# MIU60_REVB.net
KiCad netlist of a schematic drawn in EAGLE
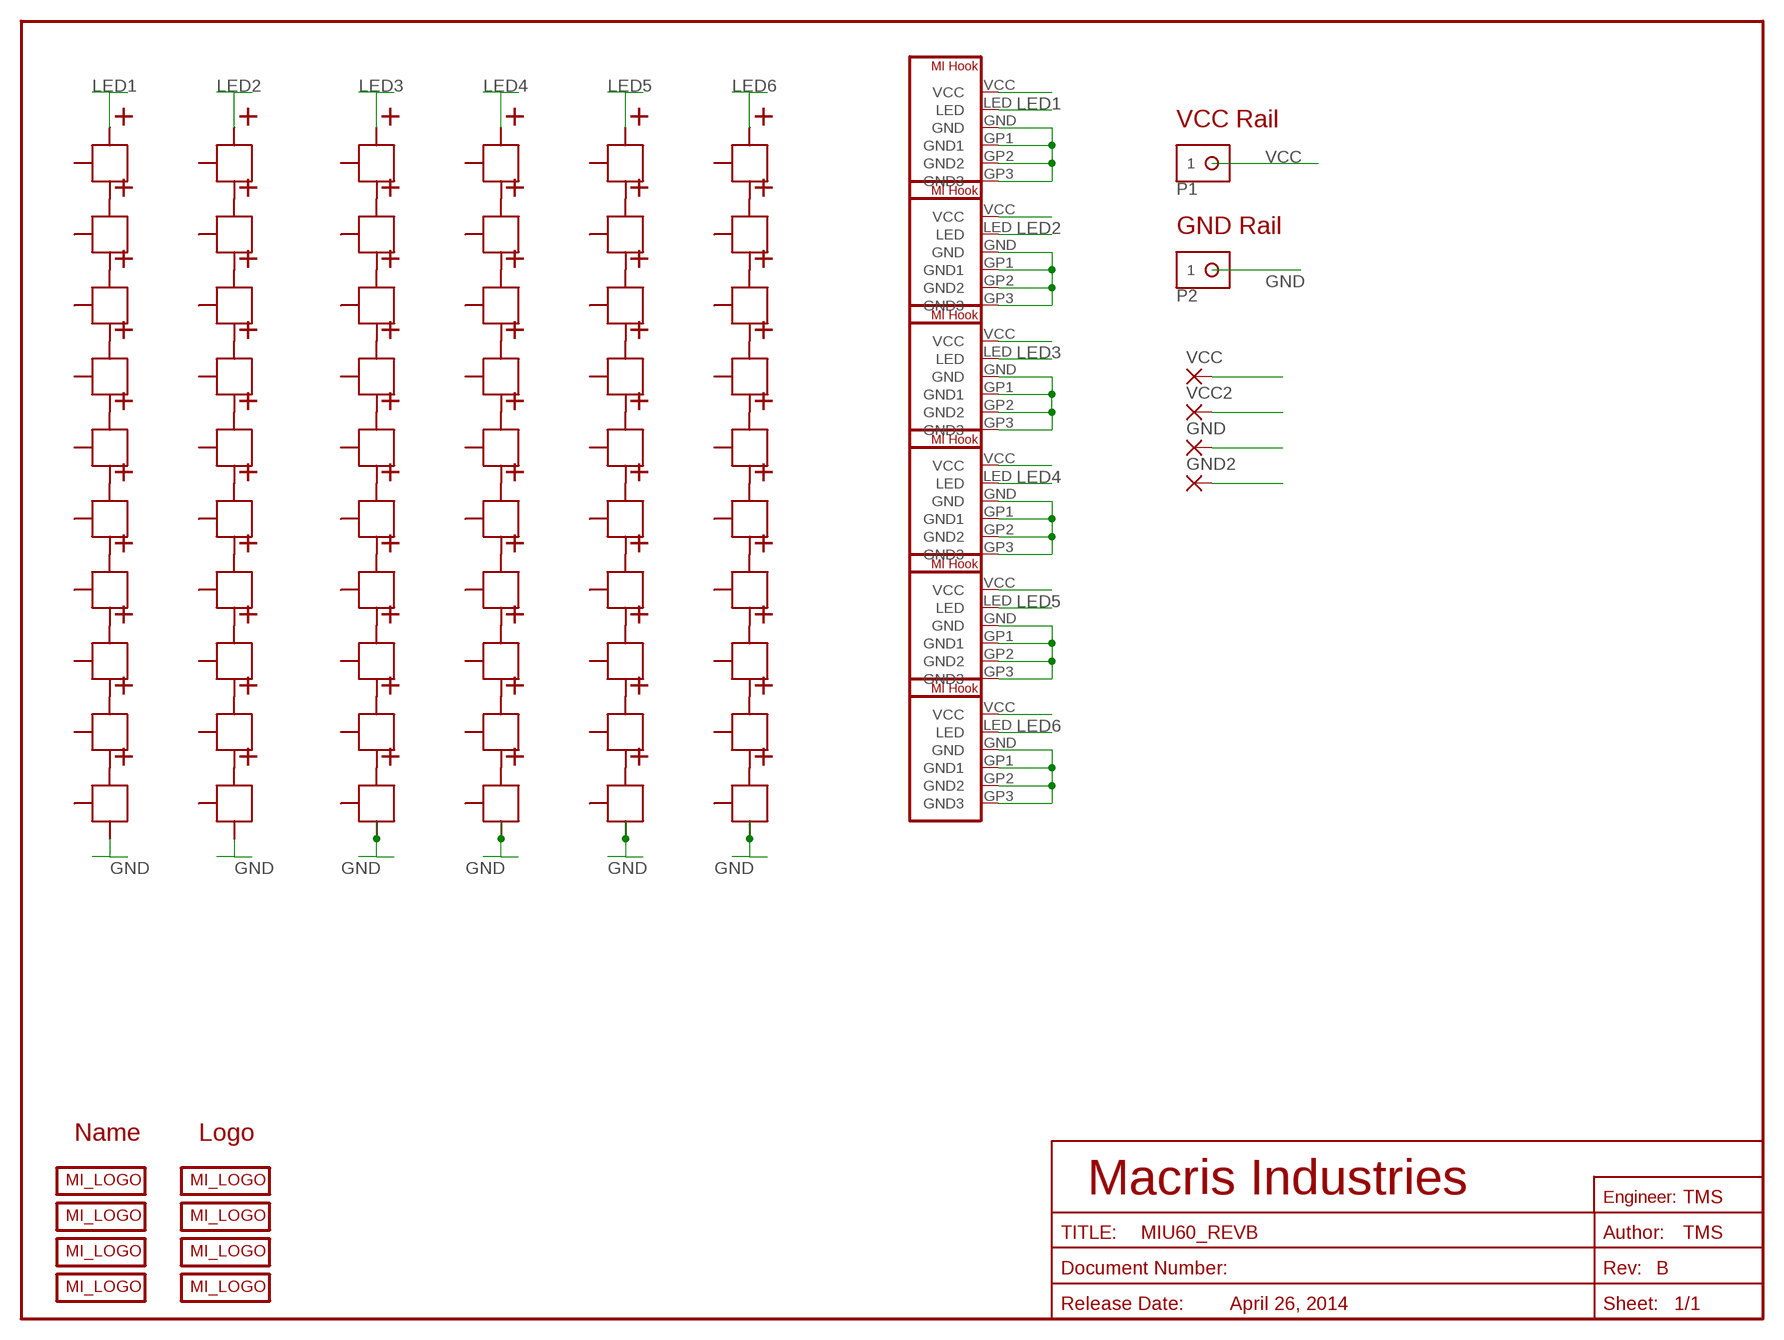
[diagram p0: schematic, sheet 1]

(export (version "E")
  (design (tool "Eeschema 10.0.6"))
  (components
    (comp (ref "GND")
      (value "SMD5")
      (footprint "eagle-import:SMD2,54-5,08")
      (libsource (lib "eagle-import") (part "SMD5"))
    )
    (comp (ref "GND2")
      (value "SMD5")
      (footprint "eagle-import:SMD2,54-5,08")
      (libsource (lib "eagle-import") (part "SMD5"))
    )
    (comp (ref "P1")
      (value "PAD-10G")
      (footprint "eagle-import:PAD_10G")
      (libsource (lib "eagle-import") (part "PAD-10G"))
    )
    (comp (ref "P2")
      (value "PAD-10G")
      (footprint "eagle-import:PAD_10G")
      (libsource (lib "eagle-import") (part "PAD-10G"))
    )
    (comp (ref "U$1")
      (value "MI_LOGO-50MIL")
      (footprint "eagle-import:MI_LOGO_NAME_2")
      (libsource (lib "eagle-import") (part "MI_LOGO-NAME_TWO"))
    )
    (comp (ref "U$2")
      (value "MI_LOGO-2014_USA")
      (footprint "eagle-import:MACRIS_USA_LOGO")
      (libsource (lib "eagle-import") (part "MI_LOGO-2014_USA"))
    )
    (comp (ref "U$3")
      (value "MI_LOGO-50MIL")
      (footprint "eagle-import:MI_LOGO_NAME_2")
      (libsource (lib "eagle-import") (part "MI_LOGO-NAME_TWO"))
    )
    (comp (ref "U$4")
      (value "MI_LOGO-2014_USA")
      (footprint "eagle-import:MACRIS_USA_LOGO")
      (libsource (lib "eagle-import") (part "MI_LOGO-2014_USA"))
    )
    (comp (ref "U$5")
      (value "MI_LOGO-50MIL")
      (footprint "eagle-import:MI_LOGO_NAME_2")
      (libsource (lib "eagle-import") (part "MI_LOGO-NAME_TWO"))
    )
    (comp (ref "U$6")
      (value "MI_LOGO-50MIL")
      (footprint "eagle-import:MI_LOGO_NAME_2")
      (libsource (lib "eagle-import") (part "MI_LOGO-NAME_TWO"))
    )
    (comp (ref "U$7")
      (value "MI_LOGO-2014_USA")
      (footprint "eagle-import:MACRIS_USA_LOGO")
      (libsource (lib "eagle-import") (part "MI_LOGO-2014_USA"))
    )
    (comp (ref "U$8")
      (value "MI_LOGO-2014_USA")
      (footprint "eagle-import:MACRIS_USA_LOGO")
      (libsource (lib "eagle-import") (part "MI_LOGO-2014_USA"))
    )
    (comp (ref "U$9")
      (value "MI_DRIVER_HOOKUP")
      (footprint "eagle-import:MI_DRIVE_HOOKUP")
      (libsource (lib "eagle-import") (part "MI_DRIVER_HOOKUP"))
    )
    (comp (ref "U$10")
      (value "MI_DRIVER_HOOKUP")
      (footprint "eagle-import:MI_DRIVE_HOOKUP")
      (libsource (lib "eagle-import") (part "MI_DRIVER_HOOKUP"))
    )
    (comp (ref "U$11")
      (value "MI_DRIVER_HOOKUP")
      (footprint "eagle-import:MI_DRIVE_HOOKUP")
      (libsource (lib "eagle-import") (part "MI_DRIVER_HOOKUP"))
    )
    (comp (ref "U$12")
      (value "MI_DRIVER_HOOKUP")
      (footprint "eagle-import:MI_DRIVE_HOOKUP")
      (libsource (lib "eagle-import") (part "MI_DRIVER_HOOKUP"))
    )
    (comp (ref "U$13")
      (value "MI_DRIVER_HOOKUP")
      (footprint "eagle-import:MI_DRIVE_HOOKUP")
      (libsource (lib "eagle-import") (part "MI_DRIVER_HOOKUP"))
    )
    (comp (ref "U$14")
      (value "MI_DRIVER_HOOKUP")
      (footprint "eagle-import:MI_DRIVE_HOOKUP")
      (libsource (lib "eagle-import") (part "MI_DRIVER_HOOKUP"))
    )
    (comp (ref "U$16")
      (value "CREE_XP")
      (footprint "eagle-import:XP")
      (libsource (lib "eagle-import") (part "CREE_XP"))
    )
    (comp (ref "U$17")
      (value "CREE_XP")
      (footprint "eagle-import:XP")
      (libsource (lib "eagle-import") (part "CREE_XP"))
    )
    (comp (ref "U$18")
      (value "CREE_XP")
      (footprint "eagle-import:XP")
      (libsource (lib "eagle-import") (part "CREE_XP"))
    )
    (comp (ref "U$19")
      (value "CREE_XP")
      (footprint "eagle-import:XP")
      (libsource (lib "eagle-import") (part "CREE_XP"))
    )
    (comp (ref "U$20")
      (value "CREE_XP")
      (footprint "eagle-import:XP")
      (libsource (lib "eagle-import") (part "CREE_XP"))
    )
    (comp (ref "U$21")
      (value "CREE_XP")
      (footprint "eagle-import:XP")
      (libsource (lib "eagle-import") (part "CREE_XP"))
    )
    (comp (ref "U$22")
      (value "CREE_XP")
      (footprint "eagle-import:XP")
      (libsource (lib "eagle-import") (part "CREE_XP"))
    )
    (comp (ref "U$23")
      (value "CREE_XP")
      (footprint "eagle-import:XP")
      (libsource (lib "eagle-import") (part "CREE_XP"))
    )
    (comp (ref "U$24")
      (value "CREE_XP")
      (footprint "eagle-import:XP")
      (libsource (lib "eagle-import") (part "CREE_XP"))
    )
    (comp (ref "U$25")
      (value "CREE_XP")
      (footprint "eagle-import:XP")
      (libsource (lib "eagle-import") (part "CREE_XP"))
    )
    (comp (ref "U$26")
      (value "CREE_XP")
      (footprint "eagle-import:XP")
      (libsource (lib "eagle-import") (part "CREE_XP"))
    )
    (comp (ref "U$27")
      (value "CREE_XP")
      (footprint "eagle-import:XP")
      (libsource (lib "eagle-import") (part "CREE_XP"))
    )
    (comp (ref "U$28")
      (value "CREE_XP")
      (footprint "eagle-import:XP")
      (libsource (lib "eagle-import") (part "CREE_XP"))
    )
    (comp (ref "U$29")
      (value "CREE_XP")
      (footprint "eagle-import:XP")
      (libsource (lib "eagle-import") (part "CREE_XP"))
    )
    (comp (ref "U$30")
      (value "CREE_XP")
      (footprint "eagle-import:XP")
      (libsource (lib "eagle-import") (part "CREE_XP"))
    )
    (comp (ref "U$31")
      (value "CREE_XP")
      (footprint "eagle-import:XP")
      (libsource (lib "eagle-import") (part "CREE_XP"))
    )
    (comp (ref "U$32")
      (value "CREE_XP")
      (footprint "eagle-import:XP")
      (libsource (lib "eagle-import") (part "CREE_XP"))
    )
    (comp (ref "U$33")
      (value "CREE_XP")
      (footprint "eagle-import:XP")
      (libsource (lib "eagle-import") (part "CREE_XP"))
    )
    (comp (ref "U$34")
      (value "CREE_XP")
      (footprint "eagle-import:XP")
      (libsource (lib "eagle-import") (part "CREE_XP"))
    )
    (comp (ref "U$35")
      (value "CREE_XP")
      (footprint "eagle-import:XP")
      (libsource (lib "eagle-import") (part "CREE_XP"))
    )
    (comp (ref "U$36")
      (value "CREE_XP")
      (footprint "eagle-import:XP")
      (libsource (lib "eagle-import") (part "CREE_XP"))
    )
    (comp (ref "U$37")
      (value "CREE_XP")
      (footprint "eagle-import:XP")
      (libsource (lib "eagle-import") (part "CREE_XP"))
    )
    (comp (ref "U$38")
      (value "CREE_XP")
      (footprint "eagle-import:XP")
      (libsource (lib "eagle-import") (part "CREE_XP"))
    )
    (comp (ref "U$39")
      (value "CREE_XP")
      (footprint "eagle-import:XP")
      (libsource (lib "eagle-import") (part "CREE_XP"))
    )
    (comp (ref "U$40")
      (value "CREE_XP")
      (footprint "eagle-import:XP")
      (libsource (lib "eagle-import") (part "CREE_XP"))
    )
    (comp (ref "U$41")
      (value "CREE_XP")
      (footprint "eagle-import:XP")
      (libsource (lib "eagle-import") (part "CREE_XP"))
    )
    (comp (ref "U$42")
      (value "CREE_XP")
      (footprint "eagle-import:XP")
      (libsource (lib "eagle-import") (part "CREE_XP"))
    )
    (comp (ref "U$43")
      (value "CREE_XP")
      (footprint "eagle-import:XP")
      (libsource (lib "eagle-import") (part "CREE_XP"))
    )
    (comp (ref "U$44")
      (value "CREE_XP")
      (footprint "eagle-import:XP")
      (libsource (lib "eagle-import") (part "CREE_XP"))
    )
    (comp (ref "U$45")
      (value "CREE_XP")
      (footprint "eagle-import:XP")
      (libsource (lib "eagle-import") (part "CREE_XP"))
    )
    (comp (ref "U$46")
      (value "CREE_XP")
      (footprint "eagle-import:XP")
      (libsource (lib "eagle-import") (part "CREE_XP"))
    )
    (comp (ref "U$47")
      (value "CREE_XP")
      (footprint "eagle-import:XP")
      (libsource (lib "eagle-import") (part "CREE_XP"))
    )
    (comp (ref "U$48")
      (value "CREE_XP")
      (footprint "eagle-import:XP")
      (libsource (lib "eagle-import") (part "CREE_XP"))
    )
    (comp (ref "U$49")
      (value "CREE_XP")
      (footprint "eagle-import:XP")
      (libsource (lib "eagle-import") (part "CREE_XP"))
    )
    (comp (ref "U$50")
      (value "CREE_XP")
      (footprint "eagle-import:XP")
      (libsource (lib "eagle-import") (part "CREE_XP"))
    )
    (comp (ref "U$51")
      (value "CREE_XP")
      (footprint "eagle-import:XP")
      (libsource (lib "eagle-import") (part "CREE_XP"))
    )
    (comp (ref "U$52")
      (value "CREE_XP")
      (footprint "eagle-import:XP")
      (libsource (lib "eagle-import") (part "CREE_XP"))
    )
    (comp (ref "U$53")
      (value "CREE_XP")
      (footprint "eagle-import:XP")
      (libsource (lib "eagle-import") (part "CREE_XP"))
    )
    (comp (ref "U$54")
      (value "CREE_XP")
      (footprint "eagle-import:XP")
      (libsource (lib "eagle-import") (part "CREE_XP"))
    )
    (comp (ref "U$55")
      (value "CREE_XP")
      (footprint "eagle-import:XP")
      (libsource (lib "eagle-import") (part "CREE_XP"))
    )
    (comp (ref "U$56")
      (value "CREE_XP")
      (footprint "eagle-import:XP")
      (libsource (lib "eagle-import") (part "CREE_XP"))
    )
    (comp (ref "U$57")
      (value "CREE_XP")
      (footprint "eagle-import:XP")
      (libsource (lib "eagle-import") (part "CREE_XP"))
    )
    (comp (ref "U$58")
      (value "CREE_XP")
      (footprint "eagle-import:XP")
      (libsource (lib "eagle-import") (part "CREE_XP"))
    )
    (comp (ref "U$59")
      (value "CREE_XP")
      (footprint "eagle-import:XP")
      (libsource (lib "eagle-import") (part "CREE_XP"))
    )
    (comp (ref "U$60")
      (value "CREE_XP")
      (footprint "eagle-import:XP")
      (libsource (lib "eagle-import") (part "CREE_XP"))
    )
    (comp (ref "U$61")
      (value "CREE_XP")
      (footprint "eagle-import:XP")
      (libsource (lib "eagle-import") (part "CREE_XP"))
    )
    (comp (ref "U$62")
      (value "CREE_XP")
      (footprint "eagle-import:XP")
      (libsource (lib "eagle-import") (part "CREE_XP"))
    )
    (comp (ref "U$63")
      (value "CREE_XP")
      (footprint "eagle-import:XP")
      (libsource (lib "eagle-import") (part "CREE_XP"))
    )
    (comp (ref "U$64")
      (value "CREE_XP")
      (footprint "eagle-import:XP")
      (libsource (lib "eagle-import") (part "CREE_XP"))
    )
    (comp (ref "U$65")
      (value "CREE_XP")
      (footprint "eagle-import:XP")
      (libsource (lib "eagle-import") (part "CREE_XP"))
    )
    (comp (ref "U$66")
      (value "CREE_XP")
      (footprint "eagle-import:XP")
      (libsource (lib "eagle-import") (part "CREE_XP"))
    )
    (comp (ref "U$67")
      (value "CREE_XP")
      (footprint "eagle-import:XP")
      (libsource (lib "eagle-import") (part "CREE_XP"))
    )
    (comp (ref "U$68")
      (value "CREE_XP")
      (footprint "eagle-import:XP")
      (libsource (lib "eagle-import") (part "CREE_XP"))
    )
    (comp (ref "U$69")
      (value "CREE_XP")
      (footprint "eagle-import:XP")
      (libsource (lib "eagle-import") (part "CREE_XP"))
    )
    (comp (ref "U$70")
      (value "CREE_XP")
      (footprint "eagle-import:XP")
      (libsource (lib "eagle-import") (part "CREE_XP"))
    )
    (comp (ref "U$71")
      (value "CREE_XP")
      (footprint "eagle-import:XP")
      (libsource (lib "eagle-import") (part "CREE_XP"))
    )
    (comp (ref "U$72")
      (value "CREE_XP")
      (footprint "eagle-import:XP")
      (libsource (lib "eagle-import") (part "CREE_XP"))
    )
    (comp (ref "U$73")
      (value "CREE_XP")
      (footprint "eagle-import:XP")
      (libsource (lib "eagle-import") (part "CREE_XP"))
    )
    (comp (ref "U$74")
      (value "CREE_XP")
      (footprint "eagle-import:XP")
      (libsource (lib "eagle-import") (part "CREE_XP"))
    )
    (comp (ref "U$75")
      (value "CREE_XP")
      (footprint "eagle-import:XP")
      (libsource (lib "eagle-import") (part "CREE_XP"))
    )
    (comp (ref "VCC")
      (value "SMD5")
      (footprint "eagle-import:SMD2,54-5,08")
      (libsource (lib "eagle-import") (part "SMD5"))
    )
    (comp (ref "VCC2")
      (value "SMD5")
      (footprint "eagle-import:SMD2,54-5,08")
      (libsource (lib "eagle-import") (part "SMD5"))
    )
  )
  (nets
    (net (code "1") (name "/GND") (class "Default")
      (node (ref "GND") (pin "1") (pinfunction "P_1") (pintype "passive"))
      (node (ref "GND2") (pin "1") (pinfunction "P_1") (pintype "passive"))
      (node (ref "P2") (pin "1") (pinfunction "1_1") (pintype "passive"))
      (node (ref "U$10") (pin "GND") (pinfunction "GND_GND") (pintype "bidirectional"))
      (node (ref "U$10") (pin "GP1") (pinfunction "GND1_GP1") (pintype "bidirectional"))
      (node (ref "U$10") (pin "GP2") (pinfunction "GND2_GP2") (pintype "bidirectional"))
      (node (ref "U$10") (pin "GP3") (pinfunction "GND3_GP3") (pintype "bidirectional"))
      (node (ref "U$11") (pin "GND") (pinfunction "GND_GND") (pintype "bidirectional"))
      (node (ref "U$11") (pin "GP1") (pinfunction "GND1_GP1") (pintype "bidirectional"))
      (node (ref "U$11") (pin "GP2") (pinfunction "GND2_GP2") (pintype "bidirectional"))
      (node (ref "U$11") (pin "GP3") (pinfunction "GND3_GP3") (pintype "bidirectional"))
      (node (ref "U$12") (pin "GND") (pinfunction "GND_GND") (pintype "bidirectional"))
      (node (ref "U$12") (pin "GP1") (pinfunction "GND1_GP1") (pintype "bidirectional"))
      (node (ref "U$12") (pin "GP2") (pinfunction "GND2_GP2") (pintype "bidirectional"))
      (node (ref "U$12") (pin "GP3") (pinfunction "GND3_GP3") (pintype "bidirectional"))
      (node (ref "U$13") (pin "GND") (pinfunction "GND_GND") (pintype "bidirectional"))
      (node (ref "U$13") (pin "GP1") (pinfunction "GND1_GP1") (pintype "bidirectional"))
      (node (ref "U$13") (pin "GP2") (pinfunction "GND2_GP2") (pintype "bidirectional"))
      (node (ref "U$13") (pin "GP3") (pinfunction "GND3_GP3") (pintype "bidirectional"))
      (node (ref "U$14") (pin "GND") (pinfunction "GND_GND") (pintype "bidirectional"))
      (node (ref "U$14") (pin "GP1") (pinfunction "GND1_GP1") (pintype "bidirectional"))
      (node (ref "U$14") (pin "GP2") (pinfunction "GND2_GP2") (pintype "bidirectional"))
      (node (ref "U$14") (pin "GP3") (pinfunction "GND3_GP3") (pintype "bidirectional"))
      (node (ref "U$25") (pin "NEGATIVE") (pinfunction "NEGATIVE_NEGATIVE") (pintype "bidirectional"))
      (node (ref "U$25") (pin "NEGATIVE1") (pinfunction "NEGATIVE_NEGATIVE1") (pintype "bidirectional"))
      (node (ref "U$35") (pin "NEGATIVE") (pinfunction "NEGATIVE_NEGATIVE") (pintype "bidirectional"))
      (node (ref "U$35") (pin "NEGATIVE1") (pinfunction "NEGATIVE_NEGATIVE1") (pintype "bidirectional"))
      (node (ref "U$45") (pin "NEGATIVE") (pinfunction "NEGATIVE_NEGATIVE") (pintype "bidirectional"))
      (node (ref "U$45") (pin "NEGATIVE1") (pinfunction "NEGATIVE_NEGATIVE1") (pintype "bidirectional"))
      (node (ref "U$55") (pin "NEGATIVE") (pinfunction "NEGATIVE_NEGATIVE") (pintype "bidirectional"))
      (node (ref "U$55") (pin "NEGATIVE1") (pinfunction "NEGATIVE_NEGATIVE1") (pintype "bidirectional"))
      (node (ref "U$65") (pin "NEGATIVE") (pinfunction "NEGATIVE_NEGATIVE") (pintype "bidirectional"))
      (node (ref "U$65") (pin "NEGATIVE1") (pinfunction "NEGATIVE_NEGATIVE1") (pintype "bidirectional"))
      (node (ref "U$75") (pin "NEGATIVE") (pinfunction "NEGATIVE_NEGATIVE") (pintype "bidirectional"))
      (node (ref "U$75") (pin "NEGATIVE1") (pinfunction "NEGATIVE_NEGATIVE1") (pintype "bidirectional"))
      (node (ref "U$9") (pin "GND") (pinfunction "GND_GND") (pintype "bidirectional"))
      (node (ref "U$9") (pin "GP1") (pinfunction "GND1_GP1") (pintype "bidirectional"))
      (node (ref "U$9") (pin "GP2") (pinfunction "GND2_GP2") (pintype "bidirectional"))
      (node (ref "U$9") (pin "GP3") (pinfunction "GND3_GP3") (pintype "bidirectional"))
    )
    (net (code "2") (name "/LED1") (class "Default")
      (node (ref "U$16") (pin "POSITIVE") (pinfunction "POSITIVE_POSITIVE") (pintype "bidirectional"))
      (node (ref "U$16") (pin "POSITIVE1") (pinfunction "POSITIVE_POSITIVE1") (pintype "bidirectional"))
      (node (ref "U$9") (pin "LED") (pinfunction "LED_LED") (pintype "bidirectional"))
    )
    (net (code "3") (name "/LED2") (class "Default")
      (node (ref "U$10") (pin "LED") (pinfunction "LED_LED") (pintype "bidirectional"))
      (node (ref "U$26") (pin "POSITIVE") (pinfunction "POSITIVE_POSITIVE") (pintype "bidirectional"))
      (node (ref "U$26") (pin "POSITIVE1") (pinfunction "POSITIVE_POSITIVE1") (pintype "bidirectional"))
    )
    (net (code "4") (name "/LED3") (class "Default")
      (node (ref "U$11") (pin "LED") (pinfunction "LED_LED") (pintype "bidirectional"))
      (node (ref "U$36") (pin "POSITIVE") (pinfunction "POSITIVE_POSITIVE") (pintype "bidirectional"))
      (node (ref "U$36") (pin "POSITIVE1") (pinfunction "POSITIVE_POSITIVE1") (pintype "bidirectional"))
    )
    (net (code "5") (name "/LED4") (class "Default")
      (node (ref "U$12") (pin "LED") (pinfunction "LED_LED") (pintype "bidirectional"))
      (node (ref "U$46") (pin "POSITIVE") (pinfunction "POSITIVE_POSITIVE") (pintype "bidirectional"))
      (node (ref "U$46") (pin "POSITIVE1") (pinfunction "POSITIVE_POSITIVE1") (pintype "bidirectional"))
    )
    (net (code "6") (name "/LED5") (class "Default")
      (node (ref "U$13") (pin "LED") (pinfunction "LED_LED") (pintype "bidirectional"))
      (node (ref "U$56") (pin "POSITIVE") (pinfunction "POSITIVE_POSITIVE") (pintype "bidirectional"))
      (node (ref "U$56") (pin "POSITIVE1") (pinfunction "POSITIVE_POSITIVE1") (pintype "bidirectional"))
    )
    (net (code "7") (name "/LED6") (class "Default")
      (node (ref "U$14") (pin "LED") (pinfunction "LED_LED") (pintype "bidirectional"))
      (node (ref "U$66") (pin "POSITIVE") (pinfunction "POSITIVE_POSITIVE") (pintype "bidirectional"))
      (node (ref "U$66") (pin "POSITIVE1") (pinfunction "POSITIVE_POSITIVE1") (pintype "bidirectional"))
    )
    (net (code "8") (name "/VCC") (class "Default")
      (node (ref "P1") (pin "1") (pinfunction "1_1") (pintype "passive"))
      (node (ref "U$10") (pin "VCC") (pinfunction "VCC_VCC") (pintype "bidirectional"))
      (node (ref "U$11") (pin "VCC") (pinfunction "VCC_VCC") (pintype "bidirectional"))
      (node (ref "U$12") (pin "VCC") (pinfunction "VCC_VCC") (pintype "bidirectional"))
      (node (ref "U$13") (pin "VCC") (pinfunction "VCC_VCC") (pintype "bidirectional"))
      (node (ref "U$14") (pin "VCC") (pinfunction "VCC_VCC") (pintype "bidirectional"))
      (node (ref "U$9") (pin "VCC") (pinfunction "VCC_VCC") (pintype "bidirectional"))
      (node (ref "VCC") (pin "1") (pinfunction "P_1") (pintype "passive"))
      (node (ref "VCC2") (pin "1") (pinfunction "P_1") (pintype "passive"))
    )
    (net (code "9") (name "Net-(U$16-NEGATIVE-PadNEGATIVE1)") (class "Default")
      (node (ref "U$16") (pin "NEGATIVE") (pinfunction "NEGATIVE_NEGATIVE") (pintype "bidirectional"))
      (node (ref "U$16") (pin "NEGATIVE1") (pinfunction "NEGATIVE_NEGATIVE1") (pintype "bidirectional"))
      (node (ref "U$17") (pin "POSITIVE") (pinfunction "POSITIVE_POSITIVE") (pintype "bidirectional"))
      (node (ref "U$17") (pin "POSITIVE1") (pinfunction "POSITIVE_POSITIVE1") (pintype "bidirectional"))
    )
    (net (code "10") (name "Net-(U$17-NEGATIVE-PadNEGATIVE1)") (class "Default")
      (node (ref "U$17") (pin "NEGATIVE") (pinfunction "NEGATIVE_NEGATIVE") (pintype "bidirectional"))
      (node (ref "U$17") (pin "NEGATIVE1") (pinfunction "NEGATIVE_NEGATIVE1") (pintype "bidirectional"))
      (node (ref "U$18") (pin "POSITIVE") (pinfunction "POSITIVE_POSITIVE") (pintype "bidirectional"))
      (node (ref "U$18") (pin "POSITIVE1") (pinfunction "POSITIVE_POSITIVE1") (pintype "bidirectional"))
    )
    (net (code "11") (name "Net-(U$18-NEGATIVE-PadNEGATIVE1)") (class "Default")
      (node (ref "U$18") (pin "NEGATIVE") (pinfunction "NEGATIVE_NEGATIVE") (pintype "bidirectional"))
      (node (ref "U$18") (pin "NEGATIVE1") (pinfunction "NEGATIVE_NEGATIVE1") (pintype "bidirectional"))
      (node (ref "U$19") (pin "POSITIVE") (pinfunction "POSITIVE_POSITIVE") (pintype "bidirectional"))
      (node (ref "U$19") (pin "POSITIVE1") (pinfunction "POSITIVE_POSITIVE1") (pintype "bidirectional"))
    )
    (net (code "12") (name "Net-(U$19-NEGATIVE-PadNEGATIVE1)") (class "Default")
      (node (ref "U$19") (pin "NEGATIVE") (pinfunction "NEGATIVE_NEGATIVE") (pintype "bidirectional"))
      (node (ref "U$19") (pin "NEGATIVE1") (pinfunction "NEGATIVE_NEGATIVE1") (pintype "bidirectional"))
      (node (ref "U$20") (pin "POSITIVE") (pinfunction "POSITIVE_POSITIVE") (pintype "bidirectional"))
      (node (ref "U$20") (pin "POSITIVE1") (pinfunction "POSITIVE_POSITIVE1") (pintype "bidirectional"))
    )
    (net (code "13") (name "Net-(U$20-NEGATIVE-PadNEGATIVE1)") (class "Default")
      (node (ref "U$20") (pin "NEGATIVE") (pinfunction "NEGATIVE_NEGATIVE") (pintype "bidirectional"))
      (node (ref "U$20") (pin "NEGATIVE1") (pinfunction "NEGATIVE_NEGATIVE1") (pintype "bidirectional"))
      (node (ref "U$21") (pin "POSITIVE") (pinfunction "POSITIVE_POSITIVE") (pintype "bidirectional"))
      (node (ref "U$21") (pin "POSITIVE1") (pinfunction "POSITIVE_POSITIVE1") (pintype "bidirectional"))
    )
    (net (code "14") (name "Net-(U$21-NEGATIVE-PadNEGATIVE1)") (class "Default")
      (node (ref "U$21") (pin "NEGATIVE") (pinfunction "NEGATIVE_NEGATIVE") (pintype "bidirectional"))
      (node (ref "U$21") (pin "NEGATIVE1") (pinfunction "NEGATIVE_NEGATIVE1") (pintype "bidirectional"))
      (node (ref "U$22") (pin "POSITIVE") (pinfunction "POSITIVE_POSITIVE") (pintype "bidirectional"))
      (node (ref "U$22") (pin "POSITIVE1") (pinfunction "POSITIVE_POSITIVE1") (pintype "bidirectional"))
    )
    (net (code "15") (name "Net-(U$22-NEGATIVE-PadNEGATIVE1)") (class "Default")
      (node (ref "U$22") (pin "NEGATIVE") (pinfunction "NEGATIVE_NEGATIVE") (pintype "bidirectional"))
      (node (ref "U$22") (pin "NEGATIVE1") (pinfunction "NEGATIVE_NEGATIVE1") (pintype "bidirectional"))
      (node (ref "U$23") (pin "POSITIVE") (pinfunction "POSITIVE_POSITIVE") (pintype "bidirectional"))
      (node (ref "U$23") (pin "POSITIVE1") (pinfunction "POSITIVE_POSITIVE1") (pintype "bidirectional"))
    )
    (net (code "16") (name "Net-(U$23-NEGATIVE-PadNEGATIVE1)") (class "Default")
      (node (ref "U$23") (pin "NEGATIVE") (pinfunction "NEGATIVE_NEGATIVE") (pintype "bidirectional"))
      (node (ref "U$23") (pin "NEGATIVE1") (pinfunction "NEGATIVE_NEGATIVE1") (pintype "bidirectional"))
      (node (ref "U$24") (pin "POSITIVE") (pinfunction "POSITIVE_POSITIVE") (pintype "bidirectional"))
      (node (ref "U$24") (pin "POSITIVE1") (pinfunction "POSITIVE_POSITIVE1") (pintype "bidirectional"))
    )
    (net (code "17") (name "Net-(U$24-NEGATIVE-PadNEGATIVE1)") (class "Default")
      (node (ref "U$24") (pin "NEGATIVE") (pinfunction "NEGATIVE_NEGATIVE") (pintype "bidirectional"))
      (node (ref "U$24") (pin "NEGATIVE1") (pinfunction "NEGATIVE_NEGATIVE1") (pintype "bidirectional"))
      (node (ref "U$25") (pin "POSITIVE") (pinfunction "POSITIVE_POSITIVE") (pintype "bidirectional"))
      (node (ref "U$25") (pin "POSITIVE1") (pinfunction "POSITIVE_POSITIVE1") (pintype "bidirectional"))
    )
    (net (code "18") (name "Net-(U$26-NEGATIVE-PadNEGATIVE1)") (class "Default")
      (node (ref "U$26") (pin "NEGATIVE") (pinfunction "NEGATIVE_NEGATIVE") (pintype "bidirectional"))
      (node (ref "U$26") (pin "NEGATIVE1") (pinfunction "NEGATIVE_NEGATIVE1") (pintype "bidirectional"))
      (node (ref "U$27") (pin "POSITIVE") (pinfunction "POSITIVE_POSITIVE") (pintype "bidirectional"))
      (node (ref "U$27") (pin "POSITIVE1") (pinfunction "POSITIVE_POSITIVE1") (pintype "bidirectional"))
    )
    (net (code "19") (name "Net-(U$27-NEGATIVE-PadNEGATIVE1)") (class "Default")
      (node (ref "U$27") (pin "NEGATIVE") (pinfunction "NEGATIVE_NEGATIVE") (pintype "bidirectional"))
      (node (ref "U$27") (pin "NEGATIVE1") (pinfunction "NEGATIVE_NEGATIVE1") (pintype "bidirectional"))
      (node (ref "U$28") (pin "POSITIVE") (pinfunction "POSITIVE_POSITIVE") (pintype "bidirectional"))
      (node (ref "U$28") (pin "POSITIVE1") (pinfunction "POSITIVE_POSITIVE1") (pintype "bidirectional"))
    )
    (net (code "20") (name "Net-(U$28-NEGATIVE-PadNEGATIVE1)") (class "Default")
      (node (ref "U$28") (pin "NEGATIVE") (pinfunction "NEGATIVE_NEGATIVE") (pintype "bidirectional"))
      (node (ref "U$28") (pin "NEGATIVE1") (pinfunction "NEGATIVE_NEGATIVE1") (pintype "bidirectional"))
      (node (ref "U$29") (pin "POSITIVE") (pinfunction "POSITIVE_POSITIVE") (pintype "bidirectional"))
      (node (ref "U$29") (pin "POSITIVE1") (pinfunction "POSITIVE_POSITIVE1") (pintype "bidirectional"))
    )
    (net (code "21") (name "Net-(U$29-NEGATIVE-PadNEGATIVE1)") (class "Default")
      (node (ref "U$29") (pin "NEGATIVE") (pinfunction "NEGATIVE_NEGATIVE") (pintype "bidirectional"))
      (node (ref "U$29") (pin "NEGATIVE1") (pinfunction "NEGATIVE_NEGATIVE1") (pintype "bidirectional"))
      (node (ref "U$30") (pin "POSITIVE") (pinfunction "POSITIVE_POSITIVE") (pintype "bidirectional"))
      (node (ref "U$30") (pin "POSITIVE1") (pinfunction "POSITIVE_POSITIVE1") (pintype "bidirectional"))
    )
    (net (code "22") (name "Net-(U$30-NEGATIVE-PadNEGATIVE1)") (class "Default")
      (node (ref "U$30") (pin "NEGATIVE") (pinfunction "NEGATIVE_NEGATIVE") (pintype "bidirectional"))
      (node (ref "U$30") (pin "NEGATIVE1") (pinfunction "NEGATIVE_NEGATIVE1") (pintype "bidirectional"))
      (node (ref "U$31") (pin "POSITIVE") (pinfunction "POSITIVE_POSITIVE") (pintype "bidirectional"))
      (node (ref "U$31") (pin "POSITIVE1") (pinfunction "POSITIVE_POSITIVE1") (pintype "bidirectional"))
    )
    (net (code "23") (name "Net-(U$31-NEGATIVE-PadNEGATIVE1)") (class "Default")
      (node (ref "U$31") (pin "NEGATIVE") (pinfunction "NEGATIVE_NEGATIVE") (pintype "bidirectional"))
      (node (ref "U$31") (pin "NEGATIVE1") (pinfunction "NEGATIVE_NEGATIVE1") (pintype "bidirectional"))
      (node (ref "U$32") (pin "POSITIVE") (pinfunction "POSITIVE_POSITIVE") (pintype "bidirectional"))
      (node (ref "U$32") (pin "POSITIVE1") (pinfunction "POSITIVE_POSITIVE1") (pintype "bidirectional"))
    )
    (net (code "24") (name "Net-(U$32-NEGATIVE-PadNEGATIVE1)") (class "Default")
      (node (ref "U$32") (pin "NEGATIVE") (pinfunction "NEGATIVE_NEGATIVE") (pintype "bidirectional"))
      (node (ref "U$32") (pin "NEGATIVE1") (pinfunction "NEGATIVE_NEGATIVE1") (pintype "bidirectional"))
      (node (ref "U$33") (pin "POSITIVE") (pinfunction "POSITIVE_POSITIVE") (pintype "bidirectional"))
      (node (ref "U$33") (pin "POSITIVE1") (pinfunction "POSITIVE_POSITIVE1") (pintype "bidirectional"))
    )
    (net (code "25") (name "Net-(U$33-NEGATIVE-PadNEGATIVE1)") (class "Default")
      (node (ref "U$33") (pin "NEGATIVE") (pinfunction "NEGATIVE_NEGATIVE") (pintype "bidirectional"))
      (node (ref "U$33") (pin "NEGATIVE1") (pinfunction "NEGATIVE_NEGATIVE1") (pintype "bidirectional"))
      (node (ref "U$34") (pin "POSITIVE") (pinfunction "POSITIVE_POSITIVE") (pintype "bidirectional"))
      (node (ref "U$34") (pin "POSITIVE1") (pinfunction "POSITIVE_POSITIVE1") (pintype "bidirectional"))
    )
    (net (code "26") (name "Net-(U$34-NEGATIVE-PadNEGATIVE1)") (class "Default")
      (node (ref "U$34") (pin "NEGATIVE") (pinfunction "NEGATIVE_NEGATIVE") (pintype "bidirectional"))
      (node (ref "U$34") (pin "NEGATIVE1") (pinfunction "NEGATIVE_NEGATIVE1") (pintype "bidirectional"))
      (node (ref "U$35") (pin "POSITIVE") (pinfunction "POSITIVE_POSITIVE") (pintype "bidirectional"))
      (node (ref "U$35") (pin "POSITIVE1") (pinfunction "POSITIVE_POSITIVE1") (pintype "bidirectional"))
    )
    (net (code "27") (name "Net-(U$36-NEGATIVE-PadNEGATIVE1)") (class "Default")
      (node (ref "U$36") (pin "NEGATIVE") (pinfunction "NEGATIVE_NEGATIVE") (pintype "bidirectional"))
      (node (ref "U$36") (pin "NEGATIVE1") (pinfunction "NEGATIVE_NEGATIVE1") (pintype "bidirectional"))
      (node (ref "U$37") (pin "POSITIVE") (pinfunction "POSITIVE_POSITIVE") (pintype "bidirectional"))
      (node (ref "U$37") (pin "POSITIVE1") (pinfunction "POSITIVE_POSITIVE1") (pintype "bidirectional"))
    )
    (net (code "28") (name "Net-(U$37-NEGATIVE-PadNEGATIVE1)") (class "Default")
      (node (ref "U$37") (pin "NEGATIVE") (pinfunction "NEGATIVE_NEGATIVE") (pintype "bidirectional"))
      (node (ref "U$37") (pin "NEGATIVE1") (pinfunction "NEGATIVE_NEGATIVE1") (pintype "bidirectional"))
      (node (ref "U$38") (pin "POSITIVE") (pinfunction "POSITIVE_POSITIVE") (pintype "bidirectional"))
      (node (ref "U$38") (pin "POSITIVE1") (pinfunction "POSITIVE_POSITIVE1") (pintype "bidirectional"))
    )
    (net (code "29") (name "Net-(U$38-NEGATIVE-PadNEGATIVE1)") (class "Default")
      (node (ref "U$38") (pin "NEGATIVE") (pinfunction "NEGATIVE_NEGATIVE") (pintype "bidirectional"))
      (node (ref "U$38") (pin "NEGATIVE1") (pinfunction "NEGATIVE_NEGATIVE1") (pintype "bidirectional"))
      (node (ref "U$39") (pin "POSITIVE") (pinfunction "POSITIVE_POSITIVE") (pintype "bidirectional"))
      (node (ref "U$39") (pin "POSITIVE1") (pinfunction "POSITIVE_POSITIVE1") (pintype "bidirectional"))
    )
    (net (code "30") (name "Net-(U$39-NEGATIVE-PadNEGATIVE1)") (class "Default")
      (node (ref "U$39") (pin "NEGATIVE") (pinfunction "NEGATIVE_NEGATIVE") (pintype "bidirectional"))
      (node (ref "U$39") (pin "NEGATIVE1") (pinfunction "NEGATIVE_NEGATIVE1") (pintype "bidirectional"))
      (node (ref "U$40") (pin "POSITIVE") (pinfunction "POSITIVE_POSITIVE") (pintype "bidirectional"))
      (node (ref "U$40") (pin "POSITIVE1") (pinfunction "POSITIVE_POSITIVE1") (pintype "bidirectional"))
    )
    (net (code "31") (name "Net-(U$40-NEGATIVE-PadNEGATIVE1)") (class "Default")
      (node (ref "U$40") (pin "NEGATIVE") (pinfunction "NEGATIVE_NEGATIVE") (pintype "bidirectional"))
      (node (ref "U$40") (pin "NEGATIVE1") (pinfunction "NEGATIVE_NEGATIVE1") (pintype "bidirectional"))
      (node (ref "U$41") (pin "POSITIVE") (pinfunction "POSITIVE_POSITIVE") (pintype "bidirectional"))
      (node (ref "U$41") (pin "POSITIVE1") (pinfunction "POSITIVE_POSITIVE1") (pintype "bidirectional"))
    )
    (net (code "32") (name "Net-(U$41-NEGATIVE-PadNEGATIVE1)") (class "Default")
      (node (ref "U$41") (pin "NEGATIVE") (pinfunction "NEGATIVE_NEGATIVE") (pintype "bidirectional"))
      (node (ref "U$41") (pin "NEGATIVE1") (pinfunction "NEGATIVE_NEGATIVE1") (pintype "bidirectional"))
      (node (ref "U$42") (pin "POSITIVE") (pinfunction "POSITIVE_POSITIVE") (pintype "bidirectional"))
      (node (ref "U$42") (pin "POSITIVE1") (pinfunction "POSITIVE_POSITIVE1") (pintype "bidirectional"))
    )
    (net (code "33") (name "Net-(U$42-NEGATIVE-PadNEGATIVE1)") (class "Default")
      (node (ref "U$42") (pin "NEGATIVE") (pinfunction "NEGATIVE_NEGATIVE") (pintype "bidirectional"))
      (node (ref "U$42") (pin "NEGATIVE1") (pinfunction "NEGATIVE_NEGATIVE1") (pintype "bidirectional"))
      (node (ref "U$43") (pin "POSITIVE") (pinfunction "POSITIVE_POSITIVE") (pintype "bidirectional"))
      (node (ref "U$43") (pin "POSITIVE1") (pinfunction "POSITIVE_POSITIVE1") (pintype "bidirectional"))
    )
    (net (code "34") (name "Net-(U$43-NEGATIVE-PadNEGATIVE1)") (class "Default")
      (node (ref "U$43") (pin "NEGATIVE") (pinfunction "NEGATIVE_NEGATIVE") (pintype "bidirectional"))
      (node (ref "U$43") (pin "NEGATIVE1") (pinfunction "NEGATIVE_NEGATIVE1") (pintype "bidirectional"))
      (node (ref "U$44") (pin "POSITIVE") (pinfunction "POSITIVE_POSITIVE") (pintype "bidirectional"))
      (node (ref "U$44") (pin "POSITIVE1") (pinfunction "POSITIVE_POSITIVE1") (pintype "bidirectional"))
    )
    (net (code "35") (name "Net-(U$44-NEGATIVE-PadNEGATIVE1)") (class "Default")
      (node (ref "U$44") (pin "NEGATIVE") (pinfunction "NEGATIVE_NEGATIVE") (pintype "bidirectional"))
      (node (ref "U$44") (pin "NEGATIVE1") (pinfunction "NEGATIVE_NEGATIVE1") (pintype "bidirectional"))
      (node (ref "U$45") (pin "POSITIVE") (pinfunction "POSITIVE_POSITIVE") (pintype "bidirectional"))
      (node (ref "U$45") (pin "POSITIVE1") (pinfunction "POSITIVE_POSITIVE1") (pintype "bidirectional"))
    )
    (net (code "36") (name "Net-(U$46-NEGATIVE-PadNEGATIVE1)") (class "Default")
      (node (ref "U$46") (pin "NEGATIVE") (pinfunction "NEGATIVE_NEGATIVE") (pintype "bidirectional"))
      (node (ref "U$46") (pin "NEGATIVE1") (pinfunction "NEGATIVE_NEGATIVE1") (pintype "bidirectional"))
      (node (ref "U$47") (pin "POSITIVE") (pinfunction "POSITIVE_POSITIVE") (pintype "bidirectional"))
      (node (ref "U$47") (pin "POSITIVE1") (pinfunction "POSITIVE_POSITIVE1") (pintype "bidirectional"))
    )
    (net (code "37") (name "Net-(U$47-NEGATIVE-PadNEGATIVE1)") (class "Default")
      (node (ref "U$47") (pin "NEGATIVE") (pinfunction "NEGATIVE_NEGATIVE") (pintype "bidirectional"))
      (node (ref "U$47") (pin "NEGATIVE1") (pinfunction "NEGATIVE_NEGATIVE1") (pintype "bidirectional"))
      (node (ref "U$48") (pin "POSITIVE") (pinfunction "POSITIVE_POSITIVE") (pintype "bidirectional"))
      (node (ref "U$48") (pin "POSITIVE1") (pinfunction "POSITIVE_POSITIVE1") (pintype "bidirectional"))
    )
    (net (code "38") (name "Net-(U$48-NEGATIVE-PadNEGATIVE1)") (class "Default")
      (node (ref "U$48") (pin "NEGATIVE") (pinfunction "NEGATIVE_NEGATIVE") (pintype "bidirectional"))
      (node (ref "U$48") (pin "NEGATIVE1") (pinfunction "NEGATIVE_NEGATIVE1") (pintype "bidirectional"))
      (node (ref "U$49") (pin "POSITIVE") (pinfunction "POSITIVE_POSITIVE") (pintype "bidirectional"))
      (node (ref "U$49") (pin "POSITIVE1") (pinfunction "POSITIVE_POSITIVE1") (pintype "bidirectional"))
    )
    (net (code "39") (name "Net-(U$49-NEGATIVE-PadNEGATIVE1)") (class "Default")
      (node (ref "U$49") (pin "NEGATIVE") (pinfunction "NEGATIVE_NEGATIVE") (pintype "bidirectional"))
      (node (ref "U$49") (pin "NEGATIVE1") (pinfunction "NEGATIVE_NEGATIVE1") (pintype "bidirectional"))
      (node (ref "U$50") (pin "POSITIVE") (pinfunction "POSITIVE_POSITIVE") (pintype "bidirectional"))
      (node (ref "U$50") (pin "POSITIVE1") (pinfunction "POSITIVE_POSITIVE1") (pintype "bidirectional"))
    )
    (net (code "40") (name "Net-(U$50-NEGATIVE-PadNEGATIVE1)") (class "Default")
      (node (ref "U$50") (pin "NEGATIVE") (pinfunction "NEGATIVE_NEGATIVE") (pintype "bidirectional"))
      (node (ref "U$50") (pin "NEGATIVE1") (pinfunction "NEGATIVE_NEGATIVE1") (pintype "bidirectional"))
      (node (ref "U$51") (pin "POSITIVE") (pinfunction "POSITIVE_POSITIVE") (pintype "bidirectional"))
      (node (ref "U$51") (pin "POSITIVE1") (pinfunction "POSITIVE_POSITIVE1") (pintype "bidirectional"))
    )
    (net (code "41") (name "Net-(U$51-NEGATIVE-PadNEGATIVE1)") (class "Default")
      (node (ref "U$51") (pin "NEGATIVE") (pinfunction "NEGATIVE_NEGATIVE") (pintype "bidirectional"))
      (node (ref "U$51") (pin "NEGATIVE1") (pinfunction "NEGATIVE_NEGATIVE1") (pintype "bidirectional"))
      (node (ref "U$52") (pin "POSITIVE") (pinfunction "POSITIVE_POSITIVE") (pintype "bidirectional"))
      (node (ref "U$52") (pin "POSITIVE1") (pinfunction "POSITIVE_POSITIVE1") (pintype "bidirectional"))
    )
    (net (code "42") (name "Net-(U$52-NEGATIVE-PadNEGATIVE1)") (class "Default")
      (node (ref "U$52") (pin "NEGATIVE") (pinfunction "NEGATIVE_NEGATIVE") (pintype "bidirectional"))
      (node (ref "U$52") (pin "NEGATIVE1") (pinfunction "NEGATIVE_NEGATIVE1") (pintype "bidirectional"))
      (node (ref "U$53") (pin "POSITIVE") (pinfunction "POSITIVE_POSITIVE") (pintype "bidirectional"))
      (node (ref "U$53") (pin "POSITIVE1") (pinfunction "POSITIVE_POSITIVE1") (pintype "bidirectional"))
    )
    (net (code "43") (name "Net-(U$53-NEGATIVE-PadNEGATIVE1)") (class "Default")
      (node (ref "U$53") (pin "NEGATIVE") (pinfunction "NEGATIVE_NEGATIVE") (pintype "bidirectional"))
      (node (ref "U$53") (pin "NEGATIVE1") (pinfunction "NEGATIVE_NEGATIVE1") (pintype "bidirectional"))
      (node (ref "U$54") (pin "POSITIVE") (pinfunction "POSITIVE_POSITIVE") (pintype "bidirectional"))
      (node (ref "U$54") (pin "POSITIVE1") (pinfunction "POSITIVE_POSITIVE1") (pintype "bidirectional"))
    )
    (net (code "44") (name "Net-(U$54-NEGATIVE-PadNEGATIVE1)") (class "Default")
      (node (ref "U$54") (pin "NEGATIVE") (pinfunction "NEGATIVE_NEGATIVE") (pintype "bidirectional"))
      (node (ref "U$54") (pin "NEGATIVE1") (pinfunction "NEGATIVE_NEGATIVE1") (pintype "bidirectional"))
      (node (ref "U$55") (pin "POSITIVE") (pinfunction "POSITIVE_POSITIVE") (pintype "bidirectional"))
      (node (ref "U$55") (pin "POSITIVE1") (pinfunction "POSITIVE_POSITIVE1") (pintype "bidirectional"))
    )
    (net (code "45") (name "Net-(U$56-NEGATIVE-PadNEGATIVE1)") (class "Default")
      (node (ref "U$56") (pin "NEGATIVE") (pinfunction "NEGATIVE_NEGATIVE") (pintype "bidirectional"))
      (node (ref "U$56") (pin "NEGATIVE1") (pinfunction "NEGATIVE_NEGATIVE1") (pintype "bidirectional"))
      (node (ref "U$57") (pin "POSITIVE") (pinfunction "POSITIVE_POSITIVE") (pintype "bidirectional"))
      (node (ref "U$57") (pin "POSITIVE1") (pinfunction "POSITIVE_POSITIVE1") (pintype "bidirectional"))
    )
    (net (code "46") (name "Net-(U$57-NEGATIVE-PadNEGATIVE1)") (class "Default")
      (node (ref "U$57") (pin "NEGATIVE") (pinfunction "NEGATIVE_NEGATIVE") (pintype "bidirectional"))
      (node (ref "U$57") (pin "NEGATIVE1") (pinfunction "NEGATIVE_NEGATIVE1") (pintype "bidirectional"))
      (node (ref "U$58") (pin "POSITIVE") (pinfunction "POSITIVE_POSITIVE") (pintype "bidirectional"))
      (node (ref "U$58") (pin "POSITIVE1") (pinfunction "POSITIVE_POSITIVE1") (pintype "bidirectional"))
    )
    (net (code "47") (name "Net-(U$58-NEGATIVE-PadNEGATIVE1)") (class "Default")
      (node (ref "U$58") (pin "NEGATIVE") (pinfunction "NEGATIVE_NEGATIVE") (pintype "bidirectional"))
      (node (ref "U$58") (pin "NEGATIVE1") (pinfunction "NEGATIVE_NEGATIVE1") (pintype "bidirectional"))
      (node (ref "U$59") (pin "POSITIVE") (pinfunction "POSITIVE_POSITIVE") (pintype "bidirectional"))
      (node (ref "U$59") (pin "POSITIVE1") (pinfunction "POSITIVE_POSITIVE1") (pintype "bidirectional"))
    )
    (net (code "48") (name "Net-(U$59-NEGATIVE-PadNEGATIVE1)") (class "Default")
      (node (ref "U$59") (pin "NEGATIVE") (pinfunction "NEGATIVE_NEGATIVE") (pintype "bidirectional"))
      (node (ref "U$59") (pin "NEGATIVE1") (pinfunction "NEGATIVE_NEGATIVE1") (pintype "bidirectional"))
      (node (ref "U$60") (pin "POSITIVE") (pinfunction "POSITIVE_POSITIVE") (pintype "bidirectional"))
      (node (ref "U$60") (pin "POSITIVE1") (pinfunction "POSITIVE_POSITIVE1") (pintype "bidirectional"))
    )
    (net (code "49") (name "Net-(U$60-NEGATIVE-PadNEGATIVE1)") (class "Default")
      (node (ref "U$60") (pin "NEGATIVE") (pinfunction "NEGATIVE_NEGATIVE") (pintype "bidirectional"))
      (node (ref "U$60") (pin "NEGATIVE1") (pinfunction "NEGATIVE_NEGATIVE1") (pintype "bidirectional"))
      (node (ref "U$61") (pin "POSITIVE") (pinfunction "POSITIVE_POSITIVE") (pintype "bidirectional"))
      (node (ref "U$61") (pin "POSITIVE1") (pinfunction "POSITIVE_POSITIVE1") (pintype "bidirectional"))
    )
    (net (code "50") (name "Net-(U$61-NEGATIVE-PadNEGATIVE1)") (class "Default")
      (node (ref "U$61") (pin "NEGATIVE") (pinfunction "NEGATIVE_NEGATIVE") (pintype "bidirectional"))
      (node (ref "U$61") (pin "NEGATIVE1") (pinfunction "NEGATIVE_NEGATIVE1") (pintype "bidirectional"))
      (node (ref "U$62") (pin "POSITIVE") (pinfunction "POSITIVE_POSITIVE") (pintype "bidirectional"))
      (node (ref "U$62") (pin "POSITIVE1") (pinfunction "POSITIVE_POSITIVE1") (pintype "bidirectional"))
    )
    (net (code "51") (name "Net-(U$62-NEGATIVE-PadNEGATIVE1)") (class "Default")
      (node (ref "U$62") (pin "NEGATIVE") (pinfunction "NEGATIVE_NEGATIVE") (pintype "bidirectional"))
      (node (ref "U$62") (pin "NEGATIVE1") (pinfunction "NEGATIVE_NEGATIVE1") (pintype "bidirectional"))
      (node (ref "U$63") (pin "POSITIVE") (pinfunction "POSITIVE_POSITIVE") (pintype "bidirectional"))
      (node (ref "U$63") (pin "POSITIVE1") (pinfunction "POSITIVE_POSITIVE1") (pintype "bidirectional"))
    )
    (net (code "52") (name "Net-(U$63-NEGATIVE-PadNEGATIVE1)") (class "Default")
      (node (ref "U$63") (pin "NEGATIVE") (pinfunction "NEGATIVE_NEGATIVE") (pintype "bidirectional"))
      (node (ref "U$63") (pin "NEGATIVE1") (pinfunction "NEGATIVE_NEGATIVE1") (pintype "bidirectional"))
      (node (ref "U$64") (pin "POSITIVE") (pinfunction "POSITIVE_POSITIVE") (pintype "bidirectional"))
      (node (ref "U$64") (pin "POSITIVE1") (pinfunction "POSITIVE_POSITIVE1") (pintype "bidirectional"))
    )
    (net (code "53") (name "Net-(U$64-NEGATIVE-PadNEGATIVE1)") (class "Default")
      (node (ref "U$64") (pin "NEGATIVE") (pinfunction "NEGATIVE_NEGATIVE") (pintype "bidirectional"))
      (node (ref "U$64") (pin "NEGATIVE1") (pinfunction "NEGATIVE_NEGATIVE1") (pintype "bidirectional"))
      (node (ref "U$65") (pin "POSITIVE") (pinfunction "POSITIVE_POSITIVE") (pintype "bidirectional"))
      (node (ref "U$65") (pin "POSITIVE1") (pinfunction "POSITIVE_POSITIVE1") (pintype "bidirectional"))
    )
    (net (code "54") (name "Net-(U$66-NEGATIVE-PadNEGATIVE1)") (class "Default")
      (node (ref "U$66") (pin "NEGATIVE") (pinfunction "NEGATIVE_NEGATIVE") (pintype "bidirectional"))
      (node (ref "U$66") (pin "NEGATIVE1") (pinfunction "NEGATIVE_NEGATIVE1") (pintype "bidirectional"))
      (node (ref "U$67") (pin "POSITIVE") (pinfunction "POSITIVE_POSITIVE") (pintype "bidirectional"))
      (node (ref "U$67") (pin "POSITIVE1") (pinfunction "POSITIVE_POSITIVE1") (pintype "bidirectional"))
    )
    (net (code "55") (name "Net-(U$67-NEGATIVE-PadNEGATIVE1)") (class "Default")
      (node (ref "U$67") (pin "NEGATIVE") (pinfunction "NEGATIVE_NEGATIVE") (pintype "bidirectional"))
      (node (ref "U$67") (pin "NEGATIVE1") (pinfunction "NEGATIVE_NEGATIVE1") (pintype "bidirectional"))
      (node (ref "U$68") (pin "POSITIVE") (pinfunction "POSITIVE_POSITIVE") (pintype "bidirectional"))
      (node (ref "U$68") (pin "POSITIVE1") (pinfunction "POSITIVE_POSITIVE1") (pintype "bidirectional"))
    )
    (net (code "56") (name "Net-(U$68-NEGATIVE-PadNEGATIVE1)") (class "Default")
      (node (ref "U$68") (pin "NEGATIVE") (pinfunction "NEGATIVE_NEGATIVE") (pintype "bidirectional"))
      (node (ref "U$68") (pin "NEGATIVE1") (pinfunction "NEGATIVE_NEGATIVE1") (pintype "bidirectional"))
      (node (ref "U$69") (pin "POSITIVE") (pinfunction "POSITIVE_POSITIVE") (pintype "bidirectional"))
      (node (ref "U$69") (pin "POSITIVE1") (pinfunction "POSITIVE_POSITIVE1") (pintype "bidirectional"))
    )
    (net (code "57") (name "Net-(U$69-NEGATIVE-PadNEGATIVE1)") (class "Default")
      (node (ref "U$69") (pin "NEGATIVE") (pinfunction "NEGATIVE_NEGATIVE") (pintype "bidirectional"))
      (node (ref "U$69") (pin "NEGATIVE1") (pinfunction "NEGATIVE_NEGATIVE1") (pintype "bidirectional"))
      (node (ref "U$70") (pin "POSITIVE") (pinfunction "POSITIVE_POSITIVE") (pintype "bidirectional"))
      (node (ref "U$70") (pin "POSITIVE1") (pinfunction "POSITIVE_POSITIVE1") (pintype "bidirectional"))
    )
    (net (code "58") (name "Net-(U$70-NEGATIVE-PadNEGATIVE1)") (class "Default")
      (node (ref "U$70") (pin "NEGATIVE") (pinfunction "NEGATIVE_NEGATIVE") (pintype "bidirectional"))
      (node (ref "U$70") (pin "NEGATIVE1") (pinfunction "NEGATIVE_NEGATIVE1") (pintype "bidirectional"))
      (node (ref "U$71") (pin "POSITIVE") (pinfunction "POSITIVE_POSITIVE") (pintype "bidirectional"))
      (node (ref "U$71") (pin "POSITIVE1") (pinfunction "POSITIVE_POSITIVE1") (pintype "bidirectional"))
    )
    (net (code "59") (name "Net-(U$71-NEGATIVE-PadNEGATIVE1)") (class "Default")
      (node (ref "U$71") (pin "NEGATIVE") (pinfunction "NEGATIVE_NEGATIVE") (pintype "bidirectional"))
      (node (ref "U$71") (pin "NEGATIVE1") (pinfunction "NEGATIVE_NEGATIVE1") (pintype "bidirectional"))
      (node (ref "U$72") (pin "POSITIVE") (pinfunction "POSITIVE_POSITIVE") (pintype "bidirectional"))
      (node (ref "U$72") (pin "POSITIVE1") (pinfunction "POSITIVE_POSITIVE1") (pintype "bidirectional"))
    )
    (net (code "60") (name "Net-(U$72-NEGATIVE-PadNEGATIVE1)") (class "Default")
      (node (ref "U$72") (pin "NEGATIVE") (pinfunction "NEGATIVE_NEGATIVE") (pintype "bidirectional"))
      (node (ref "U$72") (pin "NEGATIVE1") (pinfunction "NEGATIVE_NEGATIVE1") (pintype "bidirectional"))
      (node (ref "U$73") (pin "POSITIVE") (pinfunction "POSITIVE_POSITIVE") (pintype "bidirectional"))
      (node (ref "U$73") (pin "POSITIVE1") (pinfunction "POSITIVE_POSITIVE1") (pintype "bidirectional"))
    )
    (net (code "61") (name "Net-(U$73-NEGATIVE-PadNEGATIVE1)") (class "Default")
      (node (ref "U$73") (pin "NEGATIVE") (pinfunction "NEGATIVE_NEGATIVE") (pintype "bidirectional"))
      (node (ref "U$73") (pin "NEGATIVE1") (pinfunction "NEGATIVE_NEGATIVE1") (pintype "bidirectional"))
      (node (ref "U$74") (pin "POSITIVE") (pinfunction "POSITIVE_POSITIVE") (pintype "bidirectional"))
      (node (ref "U$74") (pin "POSITIVE1") (pinfunction "POSITIVE_POSITIVE1") (pintype "bidirectional"))
    )
    (net (code "62") (name "Net-(U$74-NEGATIVE-PadNEGATIVE1)") (class "Default")
      (node (ref "U$74") (pin "NEGATIVE") (pinfunction "NEGATIVE_NEGATIVE") (pintype "bidirectional"))
      (node (ref "U$74") (pin "NEGATIVE1") (pinfunction "NEGATIVE_NEGATIVE1") (pintype "bidirectional"))
      (node (ref "U$75") (pin "POSITIVE") (pinfunction "POSITIVE_POSITIVE") (pintype "bidirectional"))
      (node (ref "U$75") (pin "POSITIVE1") (pinfunction "POSITIVE_POSITIVE1") (pintype "bidirectional"))
    )
    (net (code "63") (name "unconnected-(U$16-PadTHERMAL)") (class "Default")
      (node (ref "U$16") (pin "THERMAL") (pinfunction "THERMAL_THERMAL") (pintype "bidirectional"))
    )
    (net (code "64") (name "unconnected-(U$17-PadTHERMAL)") (class "Default")
      (node (ref "U$17") (pin "THERMAL") (pinfunction "THERMAL_THERMAL") (pintype "bidirectional"))
    )
    (net (code "65") (name "unconnected-(U$18-PadTHERMAL)") (class "Default")
      (node (ref "U$18") (pin "THERMAL") (pinfunction "THERMAL_THERMAL") (pintype "bidirectional"))
    )
    (net (code "66") (name "unconnected-(U$19-PadTHERMAL)") (class "Default")
      (node (ref "U$19") (pin "THERMAL") (pinfunction "THERMAL_THERMAL") (pintype "bidirectional"))
    )
    (net (code "67") (name "unconnected-(U$20-PadTHERMAL)") (class "Default")
      (node (ref "U$20") (pin "THERMAL") (pinfunction "THERMAL_THERMAL") (pintype "bidirectional"))
    )
    (net (code "68") (name "unconnected-(U$21-PadTHERMAL)") (class "Default")
      (node (ref "U$21") (pin "THERMAL") (pinfunction "THERMAL_THERMAL") (pintype "bidirectional"))
    )
    (net (code "69") (name "unconnected-(U$22-PadTHERMAL)") (class "Default")
      (node (ref "U$22") (pin "THERMAL") (pinfunction "THERMAL_THERMAL") (pintype "bidirectional"))
    )
    (net (code "70") (name "unconnected-(U$23-PadTHERMAL)") (class "Default")
      (node (ref "U$23") (pin "THERMAL") (pinfunction "THERMAL_THERMAL") (pintype "bidirectional"))
    )
    (net (code "71") (name "unconnected-(U$24-PadTHERMAL)") (class "Default")
      (node (ref "U$24") (pin "THERMAL") (pinfunction "THERMAL_THERMAL") (pintype "bidirectional"))
    )
    (net (code "72") (name "unconnected-(U$25-PadTHERMAL)") (class "Default")
      (node (ref "U$25") (pin "THERMAL") (pinfunction "THERMAL_THERMAL") (pintype "bidirectional"))
    )
    (net (code "73") (name "unconnected-(U$26-PadTHERMAL)") (class "Default")
      (node (ref "U$26") (pin "THERMAL") (pinfunction "THERMAL_THERMAL") (pintype "bidirectional"))
    )
    (net (code "74") (name "unconnected-(U$27-PadTHERMAL)") (class "Default")
      (node (ref "U$27") (pin "THERMAL") (pinfunction "THERMAL_THERMAL") (pintype "bidirectional"))
    )
    (net (code "75") (name "unconnected-(U$28-PadTHERMAL)") (class "Default")
      (node (ref "U$28") (pin "THERMAL") (pinfunction "THERMAL_THERMAL") (pintype "bidirectional"))
    )
    (net (code "76") (name "unconnected-(U$29-PadTHERMAL)") (class "Default")
      (node (ref "U$29") (pin "THERMAL") (pinfunction "THERMAL_THERMAL") (pintype "bidirectional"))
    )
    (net (code "77") (name "unconnected-(U$30-PadTHERMAL)") (class "Default")
      (node (ref "U$30") (pin "THERMAL") (pinfunction "THERMAL_THERMAL") (pintype "bidirectional"))
    )
    (net (code "78") (name "unconnected-(U$31-PadTHERMAL)") (class "Default")
      (node (ref "U$31") (pin "THERMAL") (pinfunction "THERMAL_THERMAL") (pintype "bidirectional"))
    )
    (net (code "79") (name "unconnected-(U$32-PadTHERMAL)") (class "Default")
      (node (ref "U$32") (pin "THERMAL") (pinfunction "THERMAL_THERMAL") (pintype "bidirectional"))
    )
    (net (code "80") (name "unconnected-(U$33-PadTHERMAL)") (class "Default")
      (node (ref "U$33") (pin "THERMAL") (pinfunction "THERMAL_THERMAL") (pintype "bidirectional"))
    )
    (net (code "81") (name "unconnected-(U$34-PadTHERMAL)") (class "Default")
      (node (ref "U$34") (pin "THERMAL") (pinfunction "THERMAL_THERMAL") (pintype "bidirectional"))
    )
    (net (code "82") (name "unconnected-(U$35-PadTHERMAL)") (class "Default")
      (node (ref "U$35") (pin "THERMAL") (pinfunction "THERMAL_THERMAL") (pintype "bidirectional"))
    )
    (net (code "83") (name "unconnected-(U$36-PadTHERMAL)") (class "Default")
      (node (ref "U$36") (pin "THERMAL") (pinfunction "THERMAL_THERMAL") (pintype "bidirectional"))
    )
    (net (code "84") (name "unconnected-(U$37-PadTHERMAL)") (class "Default")
      (node (ref "U$37") (pin "THERMAL") (pinfunction "THERMAL_THERMAL") (pintype "bidirectional"))
    )
    (net (code "85") (name "unconnected-(U$38-PadTHERMAL)") (class "Default")
      (node (ref "U$38") (pin "THERMAL") (pinfunction "THERMAL_THERMAL") (pintype "bidirectional"))
    )
    (net (code "86") (name "unconnected-(U$39-PadTHERMAL)") (class "Default")
      (node (ref "U$39") (pin "THERMAL") (pinfunction "THERMAL_THERMAL") (pintype "bidirectional"))
    )
    (net (code "87") (name "unconnected-(U$40-PadTHERMAL)") (class "Default")
      (node (ref "U$40") (pin "THERMAL") (pinfunction "THERMAL_THERMAL") (pintype "bidirectional"))
    )
    (net (code "88") (name "unconnected-(U$41-PadTHERMAL)") (class "Default")
      (node (ref "U$41") (pin "THERMAL") (pinfunction "THERMAL_THERMAL") (pintype "bidirectional"))
    )
    (net (code "89") (name "unconnected-(U$42-PadTHERMAL)") (class "Default")
      (node (ref "U$42") (pin "THERMAL") (pinfunction "THERMAL_THERMAL") (pintype "bidirectional"))
    )
    (net (code "90") (name "unconnected-(U$43-PadTHERMAL)") (class "Default")
      (node (ref "U$43") (pin "THERMAL") (pinfunction "THERMAL_THERMAL") (pintype "bidirectional"))
    )
    (net (code "91") (name "unconnected-(U$44-PadTHERMAL)") (class "Default")
      (node (ref "U$44") (pin "THERMAL") (pinfunction "THERMAL_THERMAL") (pintype "bidirectional"))
    )
    (net (code "92") (name "unconnected-(U$45-PadTHERMAL)") (class "Default")
      (node (ref "U$45") (pin "THERMAL") (pinfunction "THERMAL_THERMAL") (pintype "bidirectional"))
    )
    (net (code "93") (name "unconnected-(U$46-PadTHERMAL)") (class "Default")
      (node (ref "U$46") (pin "THERMAL") (pinfunction "THERMAL_THERMAL") (pintype "bidirectional"))
    )
    (net (code "94") (name "unconnected-(U$47-PadTHERMAL)") (class "Default")
      (node (ref "U$47") (pin "THERMAL") (pinfunction "THERMAL_THERMAL") (pintype "bidirectional"))
    )
    (net (code "95") (name "unconnected-(U$48-PadTHERMAL)") (class "Default")
      (node (ref "U$48") (pin "THERMAL") (pinfunction "THERMAL_THERMAL") (pintype "bidirectional"))
    )
    (net (code "96") (name "unconnected-(U$49-PadTHERMAL)") (class "Default")
      (node (ref "U$49") (pin "THERMAL") (pinfunction "THERMAL_THERMAL") (pintype "bidirectional"))
    )
    (net (code "97") (name "unconnected-(U$50-PadTHERMAL)") (class "Default")
      (node (ref "U$50") (pin "THERMAL") (pinfunction "THERMAL_THERMAL") (pintype "bidirectional"))
    )
    (net (code "98") (name "unconnected-(U$51-PadTHERMAL)") (class "Default")
      (node (ref "U$51") (pin "THERMAL") (pinfunction "THERMAL_THERMAL") (pintype "bidirectional"))
    )
    (net (code "99") (name "unconnected-(U$52-PadTHERMAL)") (class "Default")
      (node (ref "U$52") (pin "THERMAL") (pinfunction "THERMAL_THERMAL") (pintype "bidirectional"))
    )
    (net (code "100") (name "unconnected-(U$53-PadTHERMAL)") (class "Default")
      (node (ref "U$53") (pin "THERMAL") (pinfunction "THERMAL_THERMAL") (pintype "bidirectional"))
    )
    (net (code "101") (name "unconnected-(U$54-PadTHERMAL)") (class "Default")
      (node (ref "U$54") (pin "THERMAL") (pinfunction "THERMAL_THERMAL") (pintype "bidirectional"))
    )
    (net (code "102") (name "unconnected-(U$55-PadTHERMAL)") (class "Default")
      (node (ref "U$55") (pin "THERMAL") (pinfunction "THERMAL_THERMAL") (pintype "bidirectional"))
    )
    (net (code "103") (name "unconnected-(U$56-PadTHERMAL)") (class "Default")
      (node (ref "U$56") (pin "THERMAL") (pinfunction "THERMAL_THERMAL") (pintype "bidirectional"))
    )
    (net (code "104") (name "unconnected-(U$57-PadTHERMAL)") (class "Default")
      (node (ref "U$57") (pin "THERMAL") (pinfunction "THERMAL_THERMAL") (pintype "bidirectional"))
    )
    (net (code "105") (name "unconnected-(U$58-PadTHERMAL)") (class "Default")
      (node (ref "U$58") (pin "THERMAL") (pinfunction "THERMAL_THERMAL") (pintype "bidirectional"))
    )
    (net (code "106") (name "unconnected-(U$59-PadTHERMAL)") (class "Default")
      (node (ref "U$59") (pin "THERMAL") (pinfunction "THERMAL_THERMAL") (pintype "bidirectional"))
    )
    (net (code "107") (name "unconnected-(U$60-PadTHERMAL)") (class "Default")
      (node (ref "U$60") (pin "THERMAL") (pinfunction "THERMAL_THERMAL") (pintype "bidirectional"))
    )
    (net (code "108") (name "unconnected-(U$61-PadTHERMAL)") (class "Default")
      (node (ref "U$61") (pin "THERMAL") (pinfunction "THERMAL_THERMAL") (pintype "bidirectional"))
    )
    (net (code "109") (name "unconnected-(U$62-PadTHERMAL)") (class "Default")
      (node (ref "U$62") (pin "THERMAL") (pinfunction "THERMAL_THERMAL") (pintype "bidirectional"))
    )
    (net (code "110") (name "unconnected-(U$63-PadTHERMAL)") (class "Default")
      (node (ref "U$63") (pin "THERMAL") (pinfunction "THERMAL_THERMAL") (pintype "bidirectional"))
    )
    (net (code "111") (name "unconnected-(U$64-PadTHERMAL)") (class "Default")
      (node (ref "U$64") (pin "THERMAL") (pinfunction "THERMAL_THERMAL") (pintype "bidirectional"))
    )
    (net (code "112") (name "unconnected-(U$65-PadTHERMAL)") (class "Default")
      (node (ref "U$65") (pin "THERMAL") (pinfunction "THERMAL_THERMAL") (pintype "bidirectional"))
    )
    (net (code "113") (name "unconnected-(U$66-PadTHERMAL)") (class "Default")
      (node (ref "U$66") (pin "THERMAL") (pinfunction "THERMAL_THERMAL") (pintype "bidirectional"))
    )
    (net (code "114") (name "unconnected-(U$67-PadTHERMAL)") (class "Default")
      (node (ref "U$67") (pin "THERMAL") (pinfunction "THERMAL_THERMAL") (pintype "bidirectional"))
    )
    (net (code "115") (name "unconnected-(U$68-PadTHERMAL)") (class "Default")
      (node (ref "U$68") (pin "THERMAL") (pinfunction "THERMAL_THERMAL") (pintype "bidirectional"))
    )
    (net (code "116") (name "unconnected-(U$69-PadTHERMAL)") (class "Default")
      (node (ref "U$69") (pin "THERMAL") (pinfunction "THERMAL_THERMAL") (pintype "bidirectional"))
    )
    (net (code "117") (name "unconnected-(U$70-PadTHERMAL)") (class "Default")
      (node (ref "U$70") (pin "THERMAL") (pinfunction "THERMAL_THERMAL") (pintype "bidirectional"))
    )
    (net (code "118") (name "unconnected-(U$71-PadTHERMAL)") (class "Default")
      (node (ref "U$71") (pin "THERMAL") (pinfunction "THERMAL_THERMAL") (pintype "bidirectional"))
    )
    (net (code "119") (name "unconnected-(U$72-PadTHERMAL)") (class "Default")
      (node (ref "U$72") (pin "THERMAL") (pinfunction "THERMAL_THERMAL") (pintype "bidirectional"))
    )
    (net (code "120") (name "unconnected-(U$73-PadTHERMAL)") (class "Default")
      (node (ref "U$73") (pin "THERMAL") (pinfunction "THERMAL_THERMAL") (pintype "bidirectional"))
    )
    (net (code "121") (name "unconnected-(U$74-PadTHERMAL)") (class "Default")
      (node (ref "U$74") (pin "THERMAL") (pinfunction "THERMAL_THERMAL") (pintype "bidirectional"))
    )
    (net (code "122") (name "unconnected-(U$75-PadTHERMAL)") (class "Default")
      (node (ref "U$75") (pin "THERMAL") (pinfunction "THERMAL_THERMAL") (pintype "bidirectional"))
    )
  )
)
